# LED_7_THANH.net
KiCad netlist of a schematic drawn in Altium Designer
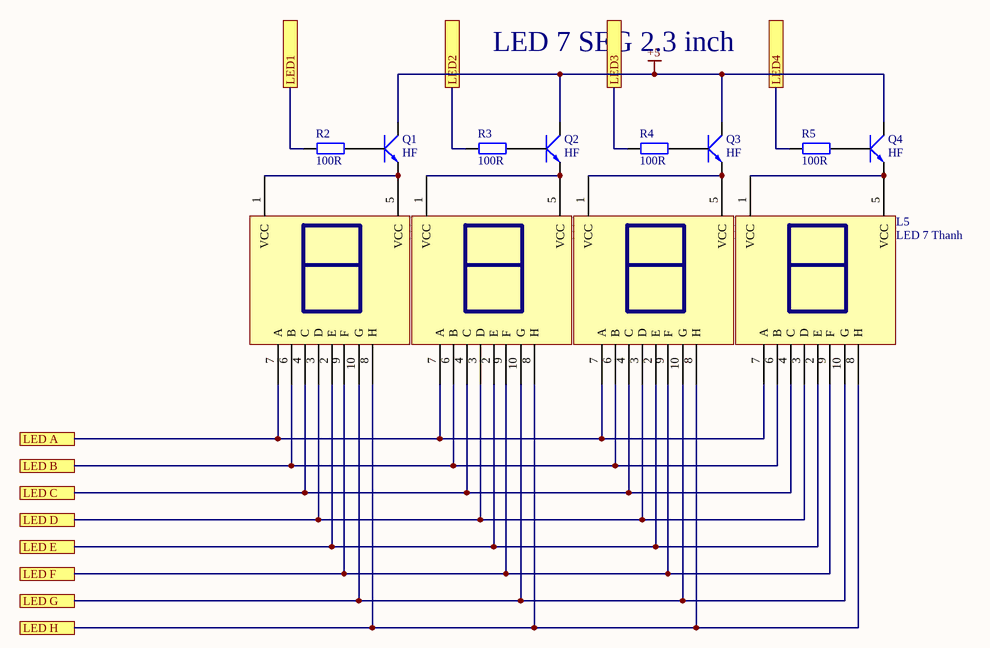
[diagram p0: LED 7 THANH.SchDoc]

(export (version "E")
  (design (tool "Eeschema 10.0.6"))
  (components
    (comp (ref "L2")
      (value "LED 7 Thanh")
      (footprint "LED7SEG_2.3inch")
      (description "Dán")
      (libsource (lib "Altium_Lib_by_KhueNguyenCreator") (part "LED 7x1 2.3inch Anot"))
    )
    (comp (ref "L3")
      (value "LED 7 Thanh")
      (footprint "LED7SEG_2.3inch")
      (description "Dán")
      (libsource (lib "Altium_Lib_by_KhueNguyenCreator") (part "LED 7x1 2.3inch Anot"))
    )
    (comp (ref "L4")
      (value "LED 7 Thanh")
      (footprint "LED7SEG_2.3inch")
      (description "Dán")
      (libsource (lib "Altium_Lib_by_KhueNguyenCreator") (part "LED 7x1 2.3inch Anot"))
    )
    (comp (ref "L5")
      (value "LED 7 Thanh")
      (footprint "LED7SEG_2.3inch")
      (description "Dán")
      (libsource (lib "Altium_Lib_by_KhueNguyenCreator") (part "LED 7x1 2.3inch Anot"))
    )
    (comp (ref "Q1")
      (value "HF")
      (footprint "SOT23")
      (description "NPN transistor")
      (libsource (lib "Altium_Lib_by_KhueNguyenCreator") (part "C1815 HF SMD"))
    )
    (comp (ref "Q2")
      (value "HF")
      (footprint "SOT23")
      (description "NPN transistor")
      (libsource (lib "Altium_Lib_by_KhueNguyenCreator") (part "C1815 HF SMD"))
    )
    (comp (ref "Q3")
      (value "HF")
      (footprint "SOT23")
      (description "NPN transistor")
      (libsource (lib "Altium_Lib_by_KhueNguyenCreator") (part "C1815 HF SMD"))
    )
    (comp (ref "Q4")
      (value "HF")
      (footprint "SOT23")
      (description "NPN transistor")
      (libsource (lib "Altium_Lib_by_KhueNguyenCreator") (part "C1815 HF SMD"))
    )
    (comp (ref "R2")
      (value "100R")
      (footprint "tro smd 0805")
      (description "Dán")
      (libsource (lib "Altium_Lib_by_KhueNguyenCreator") (part "Tro 0805 5% 100R"))
    )
    (comp (ref "R3")
      (value "100R")
      (footprint "tro smd 0805")
      (description "Dán")
      (libsource (lib "Altium_Lib_by_KhueNguyenCreator") (part "Tro 0805 5% 100R"))
    )
    (comp (ref "R4")
      (value "100R")
      (footprint "tro smd 0805")
      (description "Dán")
      (libsource (lib "Altium_Lib_by_KhueNguyenCreator") (part "Tro 0805 5% 100R"))
    )
    (comp (ref "R5")
      (value "100R")
      (footprint "tro smd 0805")
      (description "Dán")
      (libsource (lib "Altium_Lib_by_KhueNguyenCreator") (part "Tro 0805 5% 100R"))
    )
  )
  (nets
    (net (code "1") (name "+5") (class "Default")
      (node (ref "Q1") (pin "3") (pinfunction "C_3") (pintype "passive"))
      (node (ref "Q2") (pin "3") (pinfunction "C_3") (pintype "passive"))
      (node (ref "Q3") (pin "3") (pinfunction "C_3") (pintype "passive"))
      (node (ref "Q4") (pin "3") (pinfunction "C_3") (pintype "passive"))
    )
    (net (code "2") (name "/LED A") (class "Default")
      (node (ref "L2") (pin "7") (pinfunction "A_7") (pintype "passive"))
      (node (ref "L3") (pin "7") (pinfunction "A_7") (pintype "passive"))
      (node (ref "L4") (pin "7") (pinfunction "A_7") (pintype "passive"))
      (node (ref "L5") (pin "7") (pinfunction "A_7") (pintype "passive"))
    )
    (net (code "3") (name "/LED B") (class "Default")
      (node (ref "L2") (pin "6") (pinfunction "B_6") (pintype "passive"))
      (node (ref "L3") (pin "6") (pinfunction "B_6") (pintype "passive"))
      (node (ref "L4") (pin "6") (pinfunction "B_6") (pintype "passive"))
      (node (ref "L5") (pin "6") (pinfunction "B_6") (pintype "passive"))
    )
    (net (code "4") (name "/LED C") (class "Default")
      (node (ref "L2") (pin "4") (pinfunction "C_4") (pintype "passive"))
      (node (ref "L3") (pin "4") (pinfunction "C_4") (pintype "passive"))
      (node (ref "L4") (pin "4") (pinfunction "C_4") (pintype "passive"))
      (node (ref "L5") (pin "4") (pinfunction "C_4") (pintype "passive"))
    )
    (net (code "5") (name "/LED D") (class "Default")
      (node (ref "L2") (pin "3") (pinfunction "D_3") (pintype "passive"))
      (node (ref "L3") (pin "3") (pinfunction "D_3") (pintype "passive"))
      (node (ref "L4") (pin "3") (pinfunction "D_3") (pintype "passive"))
      (node (ref "L5") (pin "3") (pinfunction "D_3") (pintype "passive"))
    )
    (net (code "6") (name "/LED E") (class "Default")
      (node (ref "L2") (pin "2") (pinfunction "E_2") (pintype "passive"))
      (node (ref "L3") (pin "2") (pinfunction "E_2") (pintype "passive"))
      (node (ref "L4") (pin "2") (pinfunction "E_2") (pintype "passive"))
      (node (ref "L5") (pin "2") (pinfunction "E_2") (pintype "passive"))
    )
    (net (code "7") (name "/LED F") (class "Default")
      (node (ref "L2") (pin "9") (pinfunction "F_9") (pintype "passive"))
      (node (ref "L3") (pin "9") (pinfunction "F_9") (pintype "passive"))
      (node (ref "L4") (pin "9") (pinfunction "F_9") (pintype "passive"))
      (node (ref "L5") (pin "9") (pinfunction "F_9") (pintype "passive"))
    )
    (net (code "8") (name "/LED G") (class "Default")
      (node (ref "L2") (pin "10") (pinfunction "G_10") (pintype "passive"))
      (node (ref "L3") (pin "10") (pinfunction "G_10") (pintype "passive"))
      (node (ref "L4") (pin "10") (pinfunction "G_10") (pintype "passive"))
      (node (ref "L5") (pin "10") (pinfunction "G_10") (pintype "passive"))
    )
    (net (code "9") (name "/LED H") (class "Default")
      (node (ref "L2") (pin "8") (pinfunction "H_8") (pintype "passive"))
      (node (ref "L3") (pin "8") (pinfunction "H_8") (pintype "passive"))
      (node (ref "L4") (pin "8") (pinfunction "H_8") (pintype "passive"))
      (node (ref "L5") (pin "8") (pinfunction "H_8") (pintype "passive"))
    )
    (net (code "10") (name "/LED1") (class "Default")
      (node (ref "R2") (pin "1") (pinfunction "1_1") (pintype "passive"))
    )
    (net (code "11") (name "/LED2") (class "Default")
      (node (ref "R3") (pin "1") (pinfunction "1_1") (pintype "passive"))
    )
    (net (code "12") (name "/LED3") (class "Default")
      (node (ref "R4") (pin "1") (pinfunction "1_1") (pintype "passive"))
    )
    (net (code "13") (name "/LED4") (class "Default")
      (node (ref "R5") (pin "1") (pinfunction "1_1") (pintype "passive"))
    )
    (net (code "14") (name "Net-(Q1-B)") (class "Default")
      (node (ref "Q1") (pin "1") (pinfunction "B_1") (pintype "passive"))
      (node (ref "R2") (pin "2") (pinfunction "2_2") (pintype "passive"))
    )
    (net (code "15") (name "Net-(Q1-E)") (class "Default")
      (node (ref "L2") (pin "1") (pinfunction "VCC_1") (pintype "passive"))
      (node (ref "L2") (pin "5") (pinfunction "VCC_5") (pintype "passive"))
      (node (ref "Q1") (pin "2") (pinfunction "E_2") (pintype "passive"))
    )
    (net (code "16") (name "Net-(Q2-B)") (class "Default")
      (node (ref "Q2") (pin "1") (pinfunction "B_1") (pintype "passive"))
      (node (ref "R3") (pin "2") (pinfunction "2_2") (pintype "passive"))
    )
    (net (code "17") (name "Net-(Q2-E)") (class "Default")
      (node (ref "L3") (pin "1") (pinfunction "VCC_1") (pintype "passive"))
      (node (ref "L3") (pin "5") (pinfunction "VCC_5") (pintype "passive"))
      (node (ref "Q2") (pin "2") (pinfunction "E_2") (pintype "passive"))
    )
    (net (code "18") (name "Net-(Q3-B)") (class "Default")
      (node (ref "Q3") (pin "1") (pinfunction "B_1") (pintype "passive"))
      (node (ref "R4") (pin "2") (pinfunction "2_2") (pintype "passive"))
    )
    (net (code "19") (name "Net-(Q3-E)") (class "Default")
      (node (ref "L4") (pin "1") (pinfunction "VCC_1") (pintype "passive"))
      (node (ref "L4") (pin "5") (pinfunction "VCC_5") (pintype "passive"))
      (node (ref "Q3") (pin "2") (pinfunction "E_2") (pintype "passive"))
    )
    (net (code "20") (name "Net-(Q4-B)") (class "Default")
      (node (ref "Q4") (pin "1") (pinfunction "B_1") (pintype "passive"))
      (node (ref "R5") (pin "2") (pinfunction "2_2") (pintype "passive"))
    )
    (net (code "21") (name "Net-(Q4-E)") (class "Default")
      (node (ref "L5") (pin "1") (pinfunction "VCC_1") (pintype "passive"))
      (node (ref "L5") (pin "5") (pinfunction "VCC_5") (pintype "passive"))
      (node (ref "Q4") (pin "2") (pinfunction "E_2") (pintype "passive"))
    )
  )
)
